# MySensorMicro.net
KiCad netlist of a schematic drawn in EAGLE
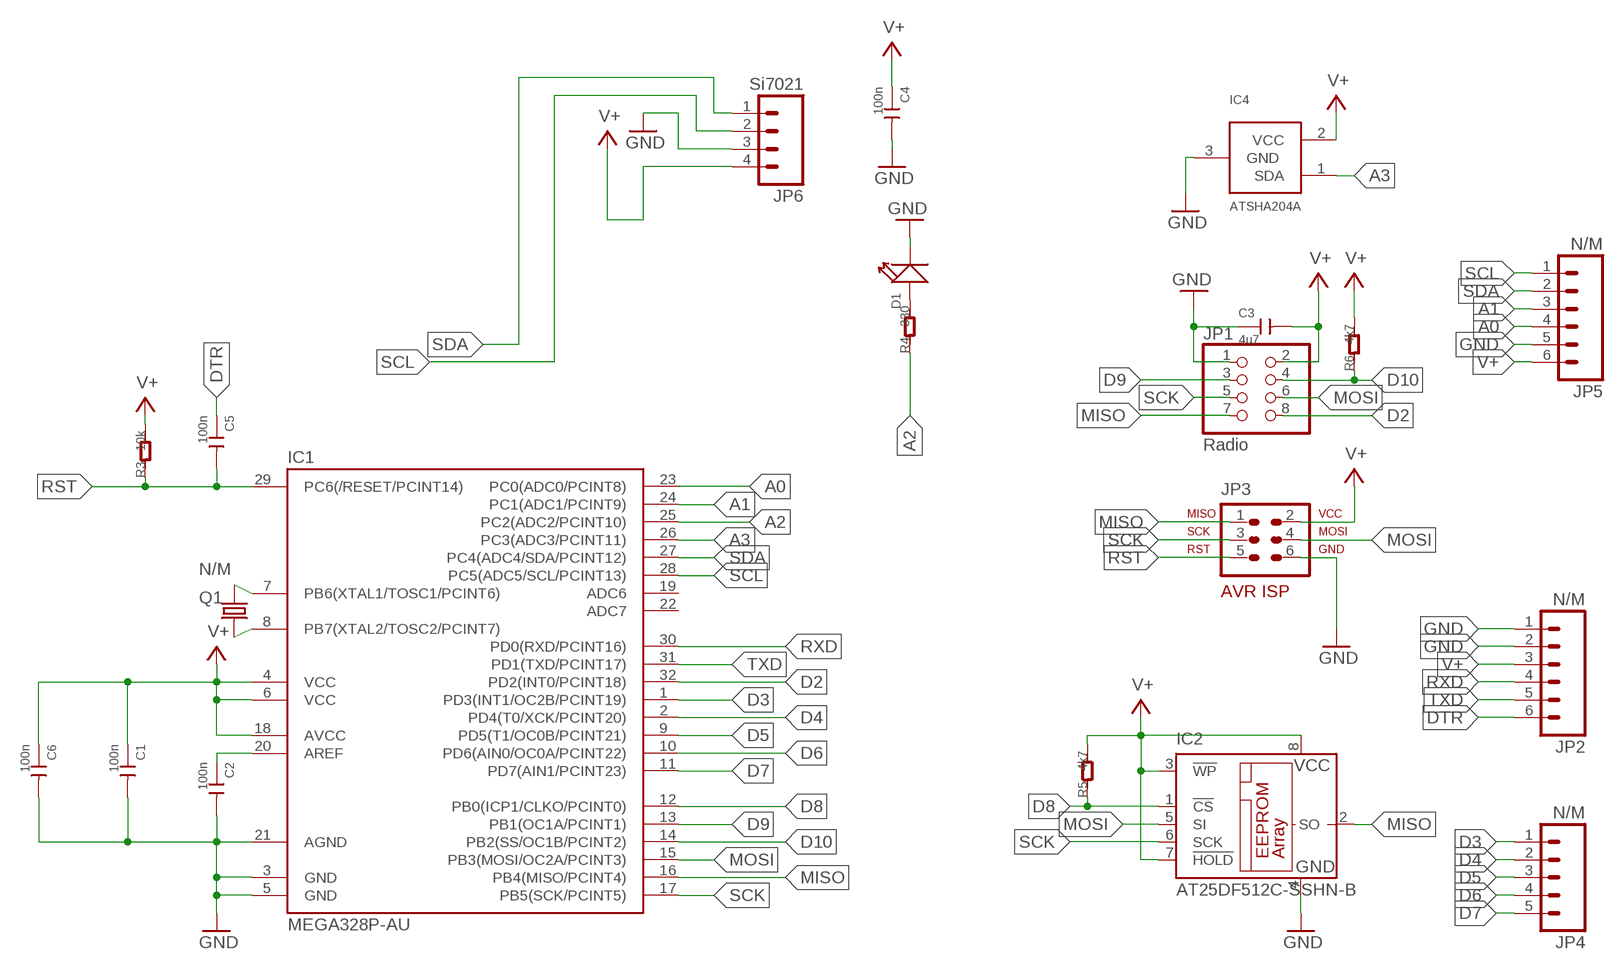
[diagram p0: schematic, sheet 1]

(export (version "E")
  (design (tool "Eeschema 10.0.6"))
  (components
    (comp (ref "C1")
      (value "100n")
      (footprint "eagle-import:C0402")
      (libsource (lib "eagle-import") (part "CAP-0402"))
    )
    (comp (ref "C2")
      (value "100n")
      (footprint "eagle-import:C0402")
      (libsource (lib "eagle-import") (part "CAP-0402"))
    )
    (comp (ref "C3")
      (value "4u7")
      (footprint "eagle-import:C0603")
      (libsource (lib "eagle-import") (part "CAP-0603"))
    )
    (comp (ref "C4")
      (value "100n")
      (footprint "eagle-import:C0402")
      (libsource (lib "eagle-import") (part "CAP-0402"))
    )
    (comp (ref "C5")
      (value "100n")
      (footprint "eagle-import:C0402")
      (libsource (lib "eagle-import") (part "CAP-0402"))
    )
    (comp (ref "C6")
      (value "100n")
      (footprint "eagle-import:C0402")
      (libsource (lib "eagle-import") (part "CAP-0402"))
    )
    (comp (ref "D1")
      (value "LED-0402")
      (footprint "eagle-import:LED-0402")
      (libsource (lib "eagle-import") (part "LED-0402"))
    )
    (comp (ref "IC1")
      (value "MEGA328P-AU")
      (footprint "eagle-import:TQFP32-08")
      (libsource (lib "eagle-import") (part "MEGA48/88/168-AU"))
    )
    (comp (ref "IC2")
      (value "AT25DF512C-SSHN-B")
      (footprint "eagle-import:SO-08")
      (fields (field (name "MF") "MICROCHIP") (field (name "MPN") "25AA080/SN"))
      (libsource (lib "eagle-import") (part "25SNAA080"))
    )
    (comp (ref "IC4")
      (value "ATSHA204A")
      (footprint "eagle-import:SOT23")
      (libsource (lib "eagle-import") (part "ATSHA204A"))
    )
    (comp (ref "JP1")
      (value "Radio")
      (footprint "eagle-import:2X04")
      (libsource (lib "eagle-import") (part "PINHD-2X4"))
    )
    (comp (ref "JP2")
      (value "N/M")
      (footprint "eagle-import:1X06_NO_SILK")
      (libsource (lib "eagle-import") (part "M06NO_SILK_FEMALE_PTH"))
    )
    (comp (ref "JP3")
      (value "N/M")
      (footprint "eagle-import:AVR-ISP-6")
      (libsource (lib "eagle-import") (part "AVR-ISP-6VERT"))
    )
    (comp (ref "JP4")
      (value "N/M")
      (footprint "eagle-import:1X05_NO_SILK")
      (libsource (lib "eagle-import") (part "M05NO_SILK"))
    )
    (comp (ref "JP5")
      (value "N/M")
      (footprint "eagle-import:1X06_NO_SILK")
      (libsource (lib "eagle-import") (part "M06NO_SILK_FEMALE_PTH"))
    )
    (comp (ref "JP6")
      (value "Si7021")
      (footprint "eagle-import:1X04")
      (libsource (lib "eagle-import") (part "M04PTH"))
    )
    (comp (ref "Q1")
      (value "N/M")
      (footprint "eagle-import:2P-L3.2XW1.5MM")
      (libsource (lib "eagle-import") (part "CRYSTAL-306010055"))
    )
    (comp (ref "R3")
      (value "10k")
      (footprint "eagle-import:R0402")
      (libsource (lib "eagle-import") (part "R-0402"))
    )
    (comp (ref "R4")
      (value "330")
      (footprint "eagle-import:R0402")
      (libsource (lib "eagle-import") (part "R-0402"))
    )
    (comp (ref "R5")
      (value "4k7")
      (footprint "eagle-import:R0402")
      (libsource (lib "eagle-import") (part "R-0402"))
    )
    (comp (ref "R6")
      (value "4k7")
      (footprint "eagle-import:R0402")
      (libsource (lib "eagle-import") (part "R-0402"))
    )
  )
  (nets
    (net (code "1") (name "A0") (class "Default")
      (node (ref "IC1") (pin "23") (pinfunction "PC0(ADC0/PCINT8)_23") (pintype "bidirectional"))
      (node (ref "JP5") (pin "4") (pinfunction "4_4") (pintype "passive"))
    )
    (net (code "2") (name "A1") (class "Default")
      (node (ref "IC1") (pin "24") (pinfunction "PC1(ADC1/PCINT9)_24") (pintype "bidirectional"))
      (node (ref "JP5") (pin "3") (pinfunction "3_3") (pintype "passive"))
    )
    (net (code "3") (name "A2") (class "Default")
      (node (ref "IC1") (pin "25") (pinfunction "PC2(ADC2/PCINT10)_25") (pintype "bidirectional"))
      (node (ref "R4") (pin "1") (pinfunction "1_1") (pintype "bidirectional"))
    )
    (net (code "4") (name "A3") (class "Default")
      (node (ref "IC1") (pin "26") (pinfunction "PC3(ADC3/PCINT11)_26") (pintype "bidirectional"))
      (node (ref "IC4") (pin "1") (pinfunction "SDA_1") (pintype "bidirectional"))
    )
    (net (code "5") (name "D2") (class "Default")
      (node (ref "IC1") (pin "32") (pinfunction "PD2(INT0/PCINT18)_32") (pintype "bidirectional"))
      (node (ref "JP1") (pin "8") (pinfunction "8_8") (pintype "passive"))
    )
    (net (code "6") (name "D3") (class "Default")
      (node (ref "IC1") (pin "1") (pinfunction "PD3(INT1/OC2B/PCINT19)_1") (pintype "bidirectional"))
      (node (ref "JP4") (pin "1") (pinfunction "1_1") (pintype "passive"))
    )
    (net (code "7") (name "D4") (class "Default")
      (node (ref "IC1") (pin "2") (pinfunction "PD4(T0/XCK/PCINT20)_2") (pintype "bidirectional"))
      (node (ref "JP4") (pin "2") (pinfunction "2_2") (pintype "passive"))
    )
    (net (code "8") (name "D5") (class "Default")
      (node (ref "IC1") (pin "9") (pinfunction "PD5(T1/OC0B/PCINT21)_9") (pintype "bidirectional"))
      (node (ref "JP4") (pin "3") (pinfunction "3_3") (pintype "passive"))
    )
    (net (code "9") (name "D6") (class "Default")
      (node (ref "IC1") (pin "10") (pinfunction "PD6(AIN0/OC0A/PCINT22)_10") (pintype "bidirectional"))
      (node (ref "JP4") (pin "4") (pinfunction "4_4") (pintype "passive"))
    )
    (net (code "10") (name "D7") (class "Default")
      (node (ref "IC1") (pin "11") (pinfunction "PD7(AIN1/PCINT23)_11") (pintype "bidirectional"))
      (node (ref "JP4") (pin "5") (pinfunction "5_5") (pintype "passive"))
    )
    (net (code "11") (name "D8") (class "Default")
      (node (ref "IC1") (pin "12") (pinfunction "PB0(ICP1/CLKO/PCINT0)_12") (pintype "bidirectional"))
      (node (ref "IC2") (pin "1") (pinfunction "~{CS}_1") (pintype "input"))
      (node (ref "R5") (pin "1") (pinfunction "1_1") (pintype "bidirectional"))
    )
    (net (code "12") (name "D9") (class "Default")
      (node (ref "IC1") (pin "13") (pinfunction "PB1(OC1A/PCINT1)_13") (pintype "bidirectional"))
      (node (ref "JP1") (pin "3") (pinfunction "3_3") (pintype "passive"))
    )
    (net (code "13") (name "D10") (class "Default")
      (node (ref "IC1") (pin "14") (pinfunction "PB2(SS/OC1B/PCINT2)_14") (pintype "bidirectional"))
      (node (ref "JP1") (pin "4") (pinfunction "4_4") (pintype "passive"))
      (node (ref "R6") (pin "1") (pinfunction "1_1") (pintype "bidirectional"))
    )
    (net (code "14") (name "DTR") (class "Default")
      (node (ref "C5") (pin "1") (pinfunction "1_1") (pintype "passive"))
      (node (ref "JP2") (pin "6") (pinfunction "6_6") (pintype "passive"))
    )
    (net (code "15") (name "GND") (class "Default")
      (node (ref "C1") (pin "2") (pinfunction "2_2") (pintype "passive"))
      (node (ref "C2") (pin "2") (pinfunction "2_2") (pintype "passive"))
      (node (ref "C3") (pin "1") (pinfunction "1_1") (pintype "passive"))
      (node (ref "C4") (pin "2") (pinfunction "2_2") (pintype "passive"))
      (node (ref "C6") (pin "2") (pinfunction "2_2") (pintype "passive"))
      (node (ref "D1") (pin "-") (pinfunction "-_-") (pintype "passive"))
      (node (ref "IC1") (pin "21") (pinfunction "AGND_21") (pintype "power_in"))
      (node (ref "IC1") (pin "3") (pinfunction "GND_3") (pintype "power_in"))
      (node (ref "IC1") (pin "5") (pinfunction "GND_5") (pintype "power_in"))
      (node (ref "IC2") (pin "4") (pinfunction "GND_4") (pintype "power_in"))
      (node (ref "IC4") (pin "3") (pinfunction "GND_3") (pintype "bidirectional"))
      (node (ref "JP1") (pin "1") (pinfunction "1_1") (pintype "passive"))
      (node (ref "JP2") (pin "1") (pinfunction "1_1") (pintype "passive"))
      (node (ref "JP2") (pin "2") (pinfunction "2_2") (pintype "passive"))
      (node (ref "JP3") (pin "6") (pinfunction "6_6") (pintype "passive"))
      (node (ref "JP5") (pin "5") (pinfunction "5_5") (pintype "passive"))
      (node (ref "JP6") (pin "3") (pinfunction "3_3") (pintype "passive"))
    )
    (net (code "16") (name "MISO") (class "Default")
      (node (ref "IC1") (pin "16") (pinfunction "PB4(MISO/PCINT4)_16") (pintype "bidirectional"))
      (node (ref "IC2") (pin "2") (pinfunction "SO_2") (pintype "bidirectional"))
      (node (ref "JP1") (pin "7") (pinfunction "7_7") (pintype "passive"))
      (node (ref "JP3") (pin "1") (pinfunction "1_1") (pintype "passive"))
    )
    (net (code "17") (name "MOSI") (class "Default")
      (node (ref "IC1") (pin "15") (pinfunction "PB3(MOSI/OC2A/PCINT3)_15") (pintype "bidirectional"))
      (node (ref "IC2") (pin "5") (pinfunction "SI_5") (pintype "input"))
      (node (ref "JP1") (pin "6") (pinfunction "6_6") (pintype "passive"))
      (node (ref "JP3") (pin "4") (pinfunction "4_4") (pintype "passive"))
    )
    (net (code "18") (name "Net-(D1-Pad+)") (class "Default")
      (node (ref "D1") (pin "+") (pinfunction "+_+") (pintype "passive"))
      (node (ref "R4") (pin "2") (pinfunction "2_2") (pintype "bidirectional"))
    )
    (net (code "19") (name "Net-(IC1-AREF)") (class "Default")
      (node (ref "C2") (pin "1") (pinfunction "1_1") (pintype "passive"))
      (node (ref "IC1") (pin "20") (pinfunction "AREF_20") (pintype "passive"))
    )
    (net (code "20") (name "Net-(IC1-PB6(XTAL1{slash}TOSC1{slash}PCINT6))") (class "Default")
      (node (ref "IC1") (pin "7") (pinfunction "PB6(XTAL1/TOSC1/PCINT6)_7") (pintype "bidirectional"))
      (node (ref "Q1") (pin "1") (pinfunction "1_1") (pintype "passive"))
    )
    (net (code "21") (name "Net-(IC1-PB7(XTAL2{slash}TOSC2{slash}PCINT7))") (class "Default")
      (node (ref "IC1") (pin "8") (pinfunction "PB7(XTAL2/TOSC2/PCINT7)_8") (pintype "bidirectional"))
      (node (ref "Q1") (pin "2") (pinfunction "2_2") (pintype "passive"))
    )
    (net (code "22") (name "RST") (class "Default")
      (node (ref "C5") (pin "2") (pinfunction "2_2") (pintype "passive"))
      (node (ref "IC1") (pin "29") (pinfunction "PC6(/RESET/PCINT14)_29") (pintype "bidirectional"))
      (node (ref "JP3") (pin "5") (pinfunction "5_5") (pintype "passive"))
      (node (ref "R3") (pin "1") (pinfunction "1_1") (pintype "bidirectional"))
    )
    (net (code "23") (name "RXD") (class "Default")
      (node (ref "IC1") (pin "30") (pinfunction "PD0(RXD/PCINT16)_30") (pintype "bidirectional"))
      (node (ref "JP2") (pin "4") (pinfunction "4_4") (pintype "passive"))
    )
    (net (code "24") (name "SCK") (class "Default")
      (node (ref "IC1") (pin "17") (pinfunction "PB5(SCK/PCINT5)_17") (pintype "bidirectional"))
      (node (ref "IC2") (pin "6") (pinfunction "SCK_6") (pintype "input"))
      (node (ref "JP1") (pin "5") (pinfunction "5_5") (pintype "passive"))
      (node (ref "JP3") (pin "3") (pinfunction "3_3") (pintype "passive"))
    )
    (net (code "25") (name "SCL") (class "Default")
      (node (ref "IC1") (pin "28") (pinfunction "PC5(ADC5/SCL/PCINT13)_28") (pintype "bidirectional"))
      (node (ref "JP5") (pin "1") (pinfunction "1_1") (pintype "passive"))
      (node (ref "JP6") (pin "2") (pinfunction "2_2") (pintype "passive"))
    )
    (net (code "26") (name "SDA") (class "Default")
      (node (ref "IC1") (pin "27") (pinfunction "PC4(ADC4/SDA/PCINT12)_27") (pintype "bidirectional"))
      (node (ref "JP5") (pin "2") (pinfunction "2_2") (pintype "passive"))
      (node (ref "JP6") (pin "1") (pinfunction "1_1") (pintype "passive"))
    )
    (net (code "27") (name "TXD") (class "Default")
      (node (ref "IC1") (pin "31") (pinfunction "PD1(TXD/PCINT17)_31") (pintype "bidirectional"))
      (node (ref "JP2") (pin "5") (pinfunction "5_5") (pintype "passive"))
    )
    (net (code "28") (name "V+") (class "Default")
      (node (ref "C1") (pin "1") (pinfunction "1_1") (pintype "passive"))
      (node (ref "C3") (pin "2") (pinfunction "2_2") (pintype "passive"))
      (node (ref "C4") (pin "1") (pinfunction "1_1") (pintype "passive"))
      (node (ref "C6") (pin "1") (pinfunction "1_1") (pintype "passive"))
      (node (ref "IC1") (pin "18") (pinfunction "AVCC_18") (pintype "passive"))
      (node (ref "IC1") (pin "4") (pinfunction "VCC_4") (pintype "power_in"))
      (node (ref "IC1") (pin "6") (pinfunction "VCC_6") (pintype "power_in"))
      (node (ref "IC2") (pin "3") (pinfunction "~{WP}_3") (pintype "input"))
      (node (ref "IC2") (pin "7") (pinfunction "~{HOLD}_7") (pintype "input"))
      (node (ref "IC2") (pin "8") (pinfunction "VCC_8") (pintype "power_in"))
      (node (ref "IC4") (pin "2") (pinfunction "VCC_2") (pintype "bidirectional"))
      (node (ref "JP1") (pin "2") (pinfunction "2_2") (pintype "passive"))
      (node (ref "JP2") (pin "3") (pinfunction "3_3") (pintype "passive"))
      (node (ref "JP3") (pin "2") (pinfunction "2_2") (pintype "passive"))
      (node (ref "JP5") (pin "6") (pinfunction "6_6") (pintype "passive"))
      (node (ref "JP6") (pin "4") (pinfunction "4_4") (pintype "passive"))
      (node (ref "R3") (pin "2") (pinfunction "2_2") (pintype "bidirectional"))
      (node (ref "R5") (pin "2") (pinfunction "2_2") (pintype "bidirectional"))
      (node (ref "R6") (pin "2") (pinfunction "2_2") (pintype "bidirectional"))
    )
    (net (code "29") (name "unconnected-(IC1-ADC6-Pad19)") (class "Default")
      (node (ref "IC1") (pin "19") (pinfunction "ADC6_19") (pintype "passive"))
    )
    (net (code "30") (name "unconnected-(IC1-ADC7-Pad22)") (class "Default")
      (node (ref "IC1") (pin "22") (pinfunction "ADC7_22") (pintype "passive"))
    )
  )
)
